# MicroSD.net
KiCad netlist of a schematic drawn in Altium Designer
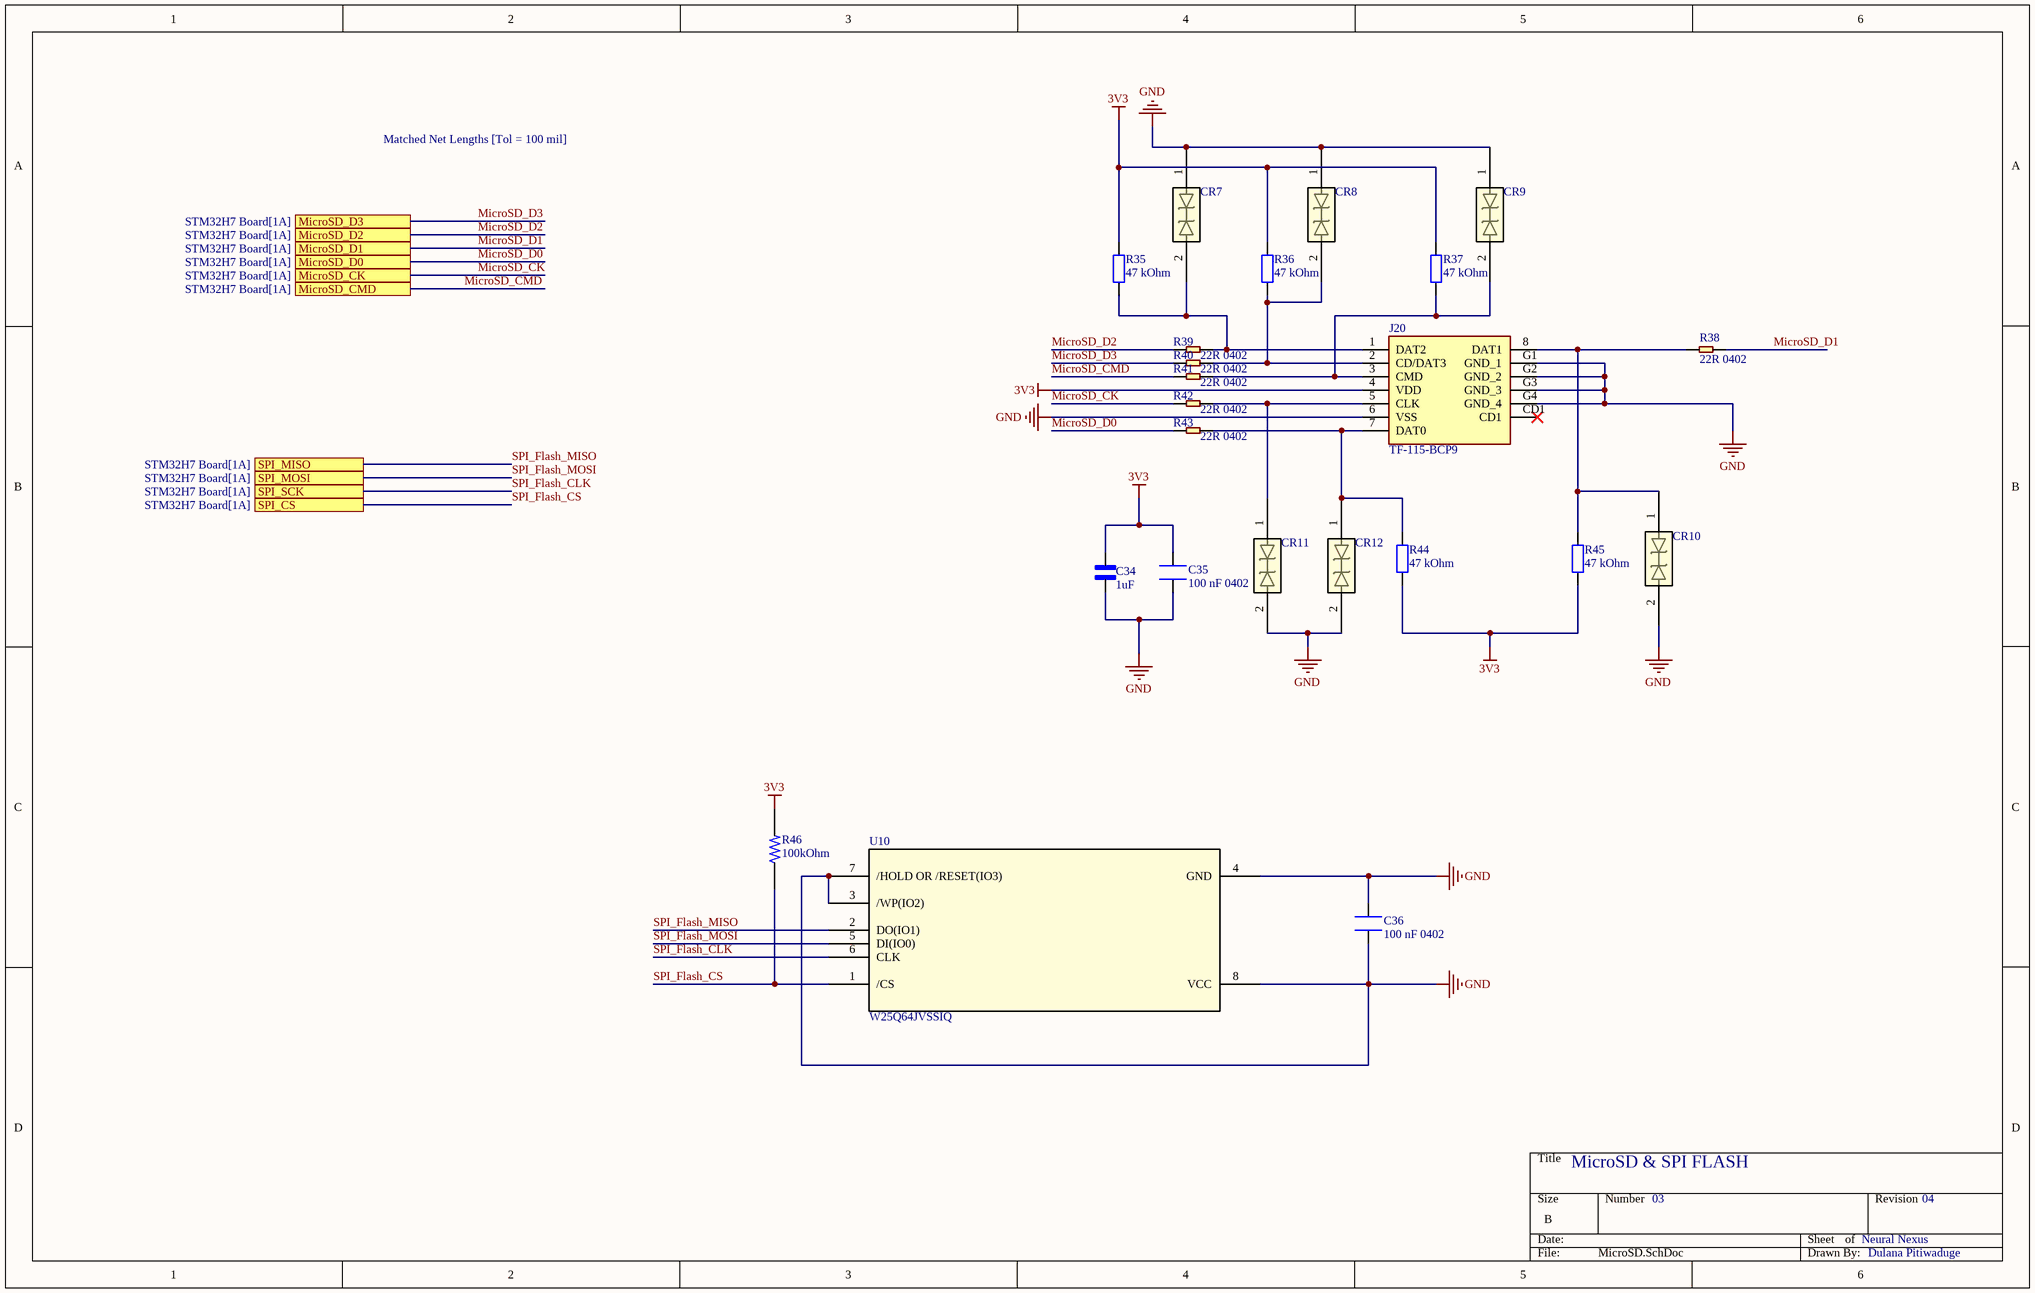
[diagram p0: MicroSD.SchDoc]

(export (version "E")
  (design (tool "Eeschema 10.0.6"))
  (components
    (comp (ref "C34")
      (value "1uF")
      (footprint "CAPC1005X55N")
      (description "1 ÂµF Â±10% 6.3V Ceramic Capacitor X5R 0402 (1005 Metric)")
      (fields (field (name "MF") "Taiyo Yuden") (field (name "MP") "JMK105BJ105KV-F"))
      (libsource (lib "Schlib1") (part "JMK105BJ105KV-F"))
    )
    (comp (ref "C35")
      (value "100 nF 0402")
      (footprint "CAPC1005X55N")
      (description "0.1 ÂµF Â±10% 10V Ceramic Capacitor X7R 0402 (1005 Metric)")
      (fields (field (name "MF") "Samsung Electro-Mechanics") (field (name "MP") "CL05B104KP5NNNC"))
      (libsource (lib "Schlib1") (part "CL05B104KP5NNNC"))
    )
    (comp (ref "C36")
      (value "100 nF 0402")
      (footprint "CAPC1005X55N")
      (description "0.1 ÂµF Â±10% 10V Ceramic Capacitor X7R 0402 (1005 Metric)")
      (fields (field (name "MF") "Samsung Electro-Mechanics") (field (name "MP") "CL05B104KP5NNNC"))
      (libsource (lib "EDR") (part "CL05B104KP5NNNC"))
    )
    (comp (ref "CR7")
      (value "SP0402B-ULC-01ETG")
      (footprint "SP0402_LTF")
      (description "Description")
      (fields (field (name "COPYRIGHT") "Copyright (C) 2025 Ultra Librarian. All rights reserved."))
      (libsource (lib "Schlib1") (part "SP0402B-ULC-01ETG"))
    )
    (comp (ref "CR8")
      (value "SP0402B-ULC-01ETG")
      (footprint "SP0402_LTF")
      (description "Description")
      (fields (field (name "COPYRIGHT") "Copyright (C) 2025 Ultra Librarian. All rights reserved."))
      (libsource (lib "Schlib1") (part "SP0402B-ULC-01ETG"))
    )
    (comp (ref "CR9")
      (value "SP0402B-ULC-01ETG")
      (footprint "SP0402_LTF")
      (description "Description")
      (fields (field (name "COPYRIGHT") "Copyright (C) 2025 Ultra Librarian. All rights reserved."))
      (libsource (lib "Schlib1") (part "SP0402B-ULC-01ETG"))
    )
    (comp (ref "CR10")
      (value "SP0402B-ULC-01ETG")
      (footprint "SP0402_LTF")
      (description "Description")
      (fields (field (name "COPYRIGHT") "Copyright (C) 2025 Ultra Librarian. All rights reserved."))
      (libsource (lib "Schlib1") (part "SP0402B-ULC-01ETG"))
    )
    (comp (ref "CR11")
      (value "SP0402B-ULC-01ETG")
      (footprint "SP0402_LTF")
      (description "Description")
      (fields (field (name "COPYRIGHT") "Copyright (C) 2025 Ultra Librarian. All rights reserved."))
      (libsource (lib "Schlib1") (part "SP0402B-ULC-01ETG"))
    )
    (comp (ref "CR12")
      (value "SP0402B-ULC-01ETG")
      (footprint "SP0402_LTF")
      (description "Description")
      (fields (field (name "COPYRIGHT") "Copyright (C) 2025 Ultra Librarian. All rights reserved."))
      (libsource (lib "Schlib1") (part "SP0402B-ULC-01ETG"))
    )
    (comp (ref "J20")
      (value "TF-115-BCP9")
      (footprint "TF115BCP9")
      (description "-25~+85 1.8mm Tin Deck MicroSD card (TF card) 260 C5191 Self bomb SMD SD Card Connectors ROHS")
      (libsource (lib "TF-115-BCP9") (part "TF-115-BCP9"))
    )
    (comp (ref "R35")
      (value "47 kOhm")
      (footprint "RESC1608X55")
      (description "47 kOhms Â±1% 0.1W, 1/10W Chip Resistor 0603 (1608 Metric) Moisture Resistant Thick Film")
      (fields (field (name "MF") "Yageo") (field (name "MP") "RC0603FR-0747KL"))
      (libsource (lib "EDR") (part "RC0603FR-0747KL"))
    )
    (comp (ref "R36")
      (value "47 kOhm")
      (footprint "RESC1608X55")
      (description "47 kOhms Â±1% 0.1W, 1/10W Chip Resistor 0603 (1608 Metric) Moisture Resistant Thick Film")
      (fields (field (name "MF") "Yageo") (field (name "MP") "RC0603FR-0747KL"))
      (libsource (lib "EDR") (part "RC0603FR-0747KL"))
    )
    (comp (ref "R37")
      (value "47 kOhm")
      (footprint "RESC1608X55")
      (description "47 kOhms Â±1% 0.1W, 1/10W Chip Resistor 0603 (1608 Metric) Moisture Resistant Thick Film")
      (fields (field (name "MF") "Yageo") (field (name "MP") "RC0603FR-0747KL"))
      (libsource (lib "EDR") (part "RC0603FR-0747KL"))
    )
    (comp (ref "R38")
      (value "22R 0402")
      (footprint "R0402")
      (description "22 Ohms Â±1% 0.063W, 1/16W Chip Resistor 0402 (1005 Metric) Moisture Resistant Thick Film")
      (fields (field (name "MF") "Yageo") (field (name "MP") "RC0402FR-0722RL"))
      (libsource (lib "Schlib1") (part "SMD-RES-22R-1%-1/16W(0402)"))
    )
    (comp (ref "R39")
      (value "22R 0402")
      (footprint "R0402")
      (description "22 Ohms Â±1% 0.063W, 1/16W Chip Resistor 0402 (1005 Metric) Moisture Resistant Thick Film")
      (fields (field (name "MF") "Yageo") (field (name "MP") "RC0402FR-0722RL"))
      (libsource (lib "Schlib1") (part "SMD-RES-22R-1%-1/16W(0402)"))
    )
    (comp (ref "R40")
      (value "22R 0402")
      (footprint "R0402")
      (description "22 Ohms Â±1% 0.063W, 1/16W Chip Resistor 0402 (1005 Metric) Moisture Resistant Thick Film")
      (fields (field (name "MF") "Yageo") (field (name "MP") "RC0402FR-0722RL"))
      (libsource (lib "Schlib1") (part "SMD-RES-22R-1%-1/16W(0402)"))
    )
    (comp (ref "R41")
      (value "22R 0402")
      (footprint "R0402")
      (description "22 Ohms Â±1% 0.063W, 1/16W Chip Resistor 0402 (1005 Metric) Moisture Resistant Thick Film")
      (fields (field (name "MF") "Yageo") (field (name "MP") "RC0402FR-0722RL"))
      (libsource (lib "Schlib1") (part "SMD-RES-22R-1%-1/16W(0402)"))
    )
    (comp (ref "R42")
      (value "22R 0402")
      (footprint "R0402")
      (description "22 Ohms Â±1% 0.063W, 1/16W Chip Resistor 0402 (1005 Metric) Moisture Resistant Thick Film")
      (fields (field (name "MF") "Yageo") (field (name "MP") "RC0402FR-0722RL"))
      (libsource (lib "Schlib1") (part "SMD-RES-22R-1%-1/16W(0402)"))
    )
    (comp (ref "R43")
      (value "22R 0402")
      (footprint "R0402")
      (description "22 Ohms Â±1% 0.063W, 1/16W Chip Resistor 0402 (1005 Metric) Moisture Resistant Thick Film")
      (fields (field (name "MF") "Yageo") (field (name "MP") "RC0402FR-0722RL"))
      (libsource (lib "Schlib1") (part "SMD-RES-22R-1%-1/16W(0402)"))
    )
    (comp (ref "R44")
      (value "47 kOhm")
      (footprint "RESC1608X55")
      (description "47 kOhms Â±1% 0.1W, 1/10W Chip Resistor 0603 (1608 Metric) Moisture Resistant Thick Film")
      (fields (field (name "MF") "Yageo") (field (name "MP") "RC0603FR-0747KL"))
      (libsource (lib "EDR") (part "RC0603FR-0747KL"))
    )
    (comp (ref "R45")
      (value "47 kOhm")
      (footprint "RESC1608X55")
      (description "47 kOhms Â±1% 0.1W, 1/10W Chip Resistor 0603 (1608 Metric) Moisture Resistant Thick Film")
      (fields (field (name "MF") "Yageo") (field (name "MP") "RC0603FR-0747KL"))
      (libsource (lib "EDR") (part "RC0603FR-0747KL"))
    )
    (comp (ref "R46")
      (value "100kOhm")
      (footprint "RESC1607X60N")
      (description "100 kOhms Â±1% 0.1W, 1/10W Chip Resistor 0603 (1608 Metric) Moisture Resistant Thick Film")
      (fields (field (name "MF") "Yageo") (field (name "MP") "RC0603FR-07100KL"))
      (libsource (lib "Schlib1") (part "RC0603FR-07100KL"))
    )
    (comp (ref "U10")
      (value "W25Q64JVSSIQ")
      (footprint "SOIC-8_5P28X5P28_WIN")
      (description "IC FLASH 64MBIT SPI/QUAD 8SOIC")
      (fields (field (name "COPYRIGHT") "Copyright (C) 2025 Ultra Librarian. All rights reserved."))
      (libsource (lib "Schlib1") (part "W25Q64JVSSIQ"))
    )
  )
  (nets
    (net (code "1") (name "/MicroSD_CK") (class "Default")
      (node (ref "R42") (pin "1") (pinfunction "1_1") (pintype "passive"))
    )
    (net (code "2") (name "/MicroSD_CMD") (class "Default")
      (node (ref "R41") (pin "1") (pinfunction "1_1") (pintype "passive"))
    )
    (net (code "3") (name "/MicroSD_D0") (class "Default")
      (node (ref "R43") (pin "1") (pinfunction "1_1") (pintype "passive"))
    )
    (net (code "4") (name "/MicroSD_D1") (class "Default")
      (node (ref "R38") (pin "2") (pinfunction "2_2") (pintype "passive"))
    )
    (net (code "5") (name "/MicroSD_D2") (class "Default")
      (node (ref "R39") (pin "1") (pinfunction "1_1") (pintype "passive"))
    )
    (net (code "6") (name "/MicroSD_D3") (class "Default")
      (node (ref "R40") (pin "1") (pinfunction "1_1") (pintype "passive"))
    )
    (net (code "7") (name "/SPI_Flash_CLK") (class "Default")
      (node (ref "U10") (pin "6") (pinfunction "CLK_6") (pintype "passive"))
    )
    (net (code "8") (name "/SPI_Flash_CS") (class "Default")
      (node (ref "R46") (pin "1") (pinfunction "1_1") (pintype "passive"))
      (node (ref "U10") (pin "1") (pinfunction "/CS_1") (pintype "passive"))
    )
    (net (code "9") (name "/SPI_Flash_MISO") (class "Default")
      (node (ref "U10") (pin "2") (pinfunction "DO(IO1)_2") (pintype "passive"))
    )
    (net (code "10") (name "/SPI_Flash_MOSI") (class "Default")
      (node (ref "U10") (pin "5") (pinfunction "DI(IO0)_5") (pintype "passive"))
    )
    (net (code "11") (name "3V3") (class "Default")
      (node (ref "C34") (pin "2") (pinfunction "2_2") (pintype "passive"))
      (node (ref "C35") (pin "2") (pinfunction "2_2") (pintype "passive"))
      (node (ref "J20") (pin "4") (pinfunction "VDD_4") (pintype "passive"))
      (node (ref "R35") (pin "2") (pinfunction "2_2") (pintype "passive"))
      (node (ref "R36") (pin "2") (pinfunction "2_2") (pintype "passive"))
      (node (ref "R37") (pin "2") (pinfunction "2_2") (pintype "passive"))
      (node (ref "R44") (pin "1") (pinfunction "1_1") (pintype "passive"))
      (node (ref "R45") (pin "1") (pinfunction "1_1") (pintype "passive"))
      (node (ref "R46") (pin "2") (pinfunction "2_2") (pintype "passive"))
    )
    (net (code "12") (name "GND") (class "Default")
      (node (ref "C34") (pin "1") (pinfunction "1_1") (pintype "passive"))
      (node (ref "C35") (pin "1") (pinfunction "1_1") (pintype "passive"))
      (node (ref "C36") (pin "1") (pinfunction "1_1") (pintype "passive"))
      (node (ref "C36") (pin "2") (pinfunction "2_2") (pintype "passive"))
      (node (ref "CR10") (pin "2") (pinfunction "2_2") (pintype "passive"))
      (node (ref "CR11") (pin "2") (pinfunction "2_2") (pintype "passive"))
      (node (ref "CR12") (pin "2") (pinfunction "2_2") (pintype "passive"))
      (node (ref "CR7") (pin "1") (pinfunction "1_1") (pintype "passive"))
      (node (ref "CR8") (pin "1") (pinfunction "1_1") (pintype "passive"))
      (node (ref "CR9") (pin "1") (pinfunction "1_1") (pintype "passive"))
      (node (ref "J20") (pin "6") (pinfunction "VSS_6") (pintype "passive"))
      (node (ref "J20") (pin "G1") (pinfunction "GND_1_G1") (pintype "passive"))
      (node (ref "J20") (pin "G2") (pinfunction "GND_2_G2") (pintype "passive"))
      (node (ref "J20") (pin "G3") (pinfunction "GND_3_G3") (pintype "passive"))
      (node (ref "J20") (pin "G4") (pinfunction "GND_4_G4") (pintype "passive"))
      (node (ref "U10") (pin "3") (pinfunction "/WP(IO2)_3") (pintype "passive"))
      (node (ref "U10") (pin "4") (pinfunction "GND_4") (pintype "power_in"))
      (node (ref "U10") (pin "7") (pinfunction "/HOLD_OR_/RESET(IO3)_7") (pintype "passive"))
      (node (ref "U10") (pin "8") (pinfunction "VCC_8") (pintype "power_in"))
    )
    (net (code "13") (name "Net-(J20-CD{slash}DAT3)") (class "Default")
      (node (ref "CR8") (pin "2") (pinfunction "2_2") (pintype "passive"))
      (node (ref "J20") (pin "2") (pinfunction "CD/DAT3_2") (pintype "passive"))
      (node (ref "R36") (pin "1") (pinfunction "1_1") (pintype "passive"))
      (node (ref "R40") (pin "2") (pinfunction "2_2") (pintype "passive"))
    )
    (net (code "14") (name "Net-(J20-CLK)") (class "Default")
      (node (ref "CR11") (pin "1") (pinfunction "1_1") (pintype "passive"))
      (node (ref "J20") (pin "5") (pinfunction "CLK_5") (pintype "passive"))
      (node (ref "R42") (pin "2") (pinfunction "2_2") (pintype "passive"))
    )
    (net (code "15") (name "Net-(J20-CMD)") (class "Default")
      (node (ref "CR9") (pin "2") (pinfunction "2_2") (pintype "passive"))
      (node (ref "J20") (pin "3") (pinfunction "CMD_3") (pintype "passive"))
      (node (ref "R37") (pin "1") (pinfunction "1_1") (pintype "passive"))
      (node (ref "R41") (pin "2") (pinfunction "2_2") (pintype "passive"))
    )
    (net (code "16") (name "Net-(J20-DAT0)") (class "Default")
      (node (ref "CR12") (pin "1") (pinfunction "1_1") (pintype "passive"))
      (node (ref "J20") (pin "7") (pinfunction "DAT0_7") (pintype "passive"))
      (node (ref "R43") (pin "2") (pinfunction "2_2") (pintype "passive"))
      (node (ref "R44") (pin "2") (pinfunction "2_2") (pintype "passive"))
    )
    (net (code "17") (name "Net-(J20-DAT1)") (class "Default")
      (node (ref "CR10") (pin "1") (pinfunction "1_1") (pintype "passive"))
      (node (ref "J20") (pin "8") (pinfunction "DAT1_8") (pintype "passive"))
      (node (ref "R38") (pin "1") (pinfunction "1_1") (pintype "passive"))
      (node (ref "R45") (pin "2") (pinfunction "2_2") (pintype "passive"))
    )
    (net (code "18") (name "Net-(J20-DAT2)") (class "Default")
      (node (ref "CR7") (pin "2") (pinfunction "2_2") (pintype "passive"))
      (node (ref "J20") (pin "1") (pinfunction "DAT2_1") (pintype "passive"))
      (node (ref "R35") (pin "1") (pinfunction "1_1") (pintype "passive"))
      (node (ref "R39") (pin "2") (pinfunction "2_2") (pintype "passive"))
    )
    (net (code "19") (name "unconnected-(J20-PadCD1)") (class "Default")
      (node (ref "J20") (pin "CD1") (pinfunction "CD1_CD1") (pintype "passive+no_connect"))
    )
  )
)
